# LMH.net
KiCad netlist of a schematic drawn in Altium Designer
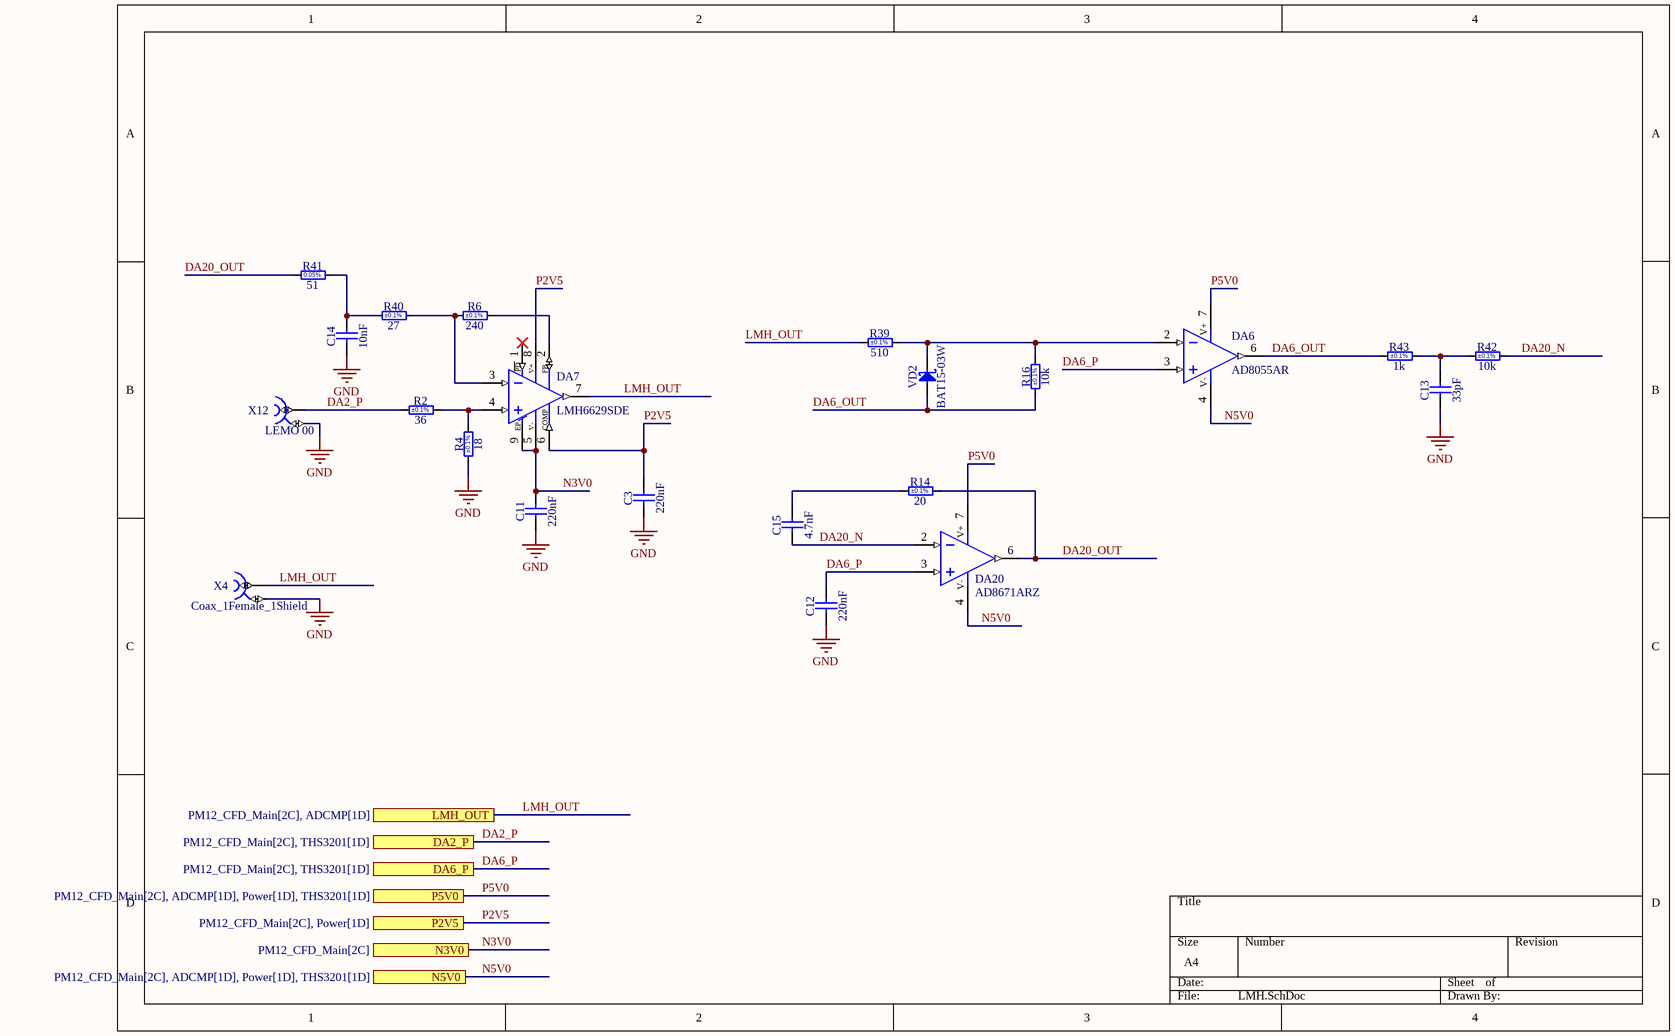
[diagram p0: LMH.SchDoc]

(export (version "E")
  (design (tool "Eeschema 10.0.6"))
  (components
    (comp (ref "C3")
      (value "220nF")
      (footprint "CAPC2012X135N")
      (description "Non-polarised capacitor")
      (fields
        (field (name "PART NUMBER") "CC0805_220NF_50V_10%_X7R")
        (field (name "VOLTAGE") "50V")
        (field (name "AUTHOR") "CERN DEM JLC")
      )
      (libsource (lib "Capacitors") (part "Capacitor - non polarized"))
    )
    (comp (ref "C11")
      (value "220nF")
      (footprint "CAPC2012X135N")
      (description "Non-polarised capacitor")
      (fields
        (field (name "PART NUMBER") "CC0805_220NF_50V_10%_X7R")
        (field (name "VOLTAGE") "50V")
        (field (name "AUTHOR") "CERN DEM JLC")
      )
      (libsource (lib "Capacitors") (part "Capacitor - non polarized"))
    )
    (comp (ref "C12")
      (value "220nF")
      (footprint "CAPC2012X135N")
      (description "Non-polarised capacitor")
      (fields
        (field (name "PART NUMBER") "CC0805_220NF_50V_10%_X7R")
        (field (name "VOLTAGE") "50V")
        (field (name "AUTHOR") "CERN DEM JLC")
      )
      (libsource (lib "Capacitors") (part "Capacitor - non polarized"))
    )
    (comp (ref "C13")
      (value "33pF")
      (footprint "CAPC2013X115N")
      (description "Non-polarised capacitor")
      (fields
        (field (name "PART NUMBER") "CC0805_33PF_200V_1%_NP0")
        (field (name "VOLTAGE") "200V")
        (field (name "AUTHOR") "CERN DEM HF")
      )
      (libsource (lib "Capacitors") (part "Capacitor - non polarized"))
    )
    (comp (ref "C14")
      (value "10nF")
      (footprint "CAPC2012X135N")
      (description "Non-polarised capacitor")
      (fields
        (field (name "PART NUMBER") "CC0805_10NF_50V_2%_C0G")
        (field (name "VOLTAGE") "50V")
        (field (name "AUTHOR") "CERN DEM HF")
      )
      (libsource (lib "Capacitors") (part "Capacitor - non polarized"))
    )
    (comp (ref "C15")
      (value "4.7nF")
      (footprint "CAPC2012X135N")
      (description "Non-polarised capacitor")
      (fields
        (field (name "PART NUMBER") "CC0805_4.7NF_250V_1%_NP0")
        (field (name "VOLTAGE") "250V")
        (field (name "AUTHOR") "CERN DEM HF")
      )
      (libsource (lib "Capacitors") (part "Capacitor - non polarized"))
    )
    (comp (ref "DA6")
      (value "AD8055AR")
      (footprint "SOIC127P600X175-8N")
      (description "Operational Amplifier")
      (fields (field (name "MANUFACTURER") "ANALOG DEVICES") (field (name "AUTHOR") "CERN DEM HF"))
      (libsource (lib "ICs And Semiconductors") (part "Operational Amplifier Type1"))
    )
    (comp (ref "DA7")
      (value "LMH6629SDE")
      (footprint "TEXAS_NGQ0008A")
      (description "Ultra-Low Noise, High-Speed Operational Amplifier with Shutdown")
      (fields (field (name "MANUFACTURER") "TEXAS INSTRUMENTS") (field (name "AUTHOR") "CERN DEM HF"))
      (libsource (lib "ICs And Semiconductors") (part "LMH6629SDE"))
    )
    (comp (ref "DA20")
      (value "AD8671ARZ")
      (footprint "SOIC127P600X175-8N")
      (description "Operational Amplifier")
      (fields
        (field (name "MANUFACTURER") "ANALOG DEVICES")
        (field (name "MANUFACTURER PART NUMBER") "AD8671AR")
        (field (name "AUTHOR") "CERN DEM JLC")
      )
      (libsource (lib "ICs And Semiconductors") (part "Operational Amplifier Type1"))
    )
    (comp (ref "R2")
      (value "36")
      (footprint "RESC1608X64N")
      (description "Resistor - 0.1%")
      (fields
        (field (name "TOLERANCE") "±0.1%")
        (field (name "PART NUMBER") "R0603_36R_0.1%_0.1W_10PPM")
        (field (name "POWER") "0.1W")
        (field (name "AUTHOR") "CERN DEM HF")
      )
      (libsource (lib "Resistors") (part "Resistor - 0.1%"))
    )
    (comp (ref "R4")
      (value "18")
      (footprint "RESC1608X64N")
      (description "Resistor - 0.1%")
      (fields
        (field (name "TOLERANCE") "±0.1%")
        (field (name "PART NUMBER") "R0603_18R_0.1%_0.1W_25PPM")
        (field (name "POWER") "0.1W")
        (field (name "AUTHOR") "CERN DEM HF")
      )
      (libsource (lib "Resistors") (part "Resistor - 0.1%"))
    )
    (comp (ref "R6")
      (value "240")
      (footprint "RESC1005X40N")
      (description "Resistor - 0.1%")
      (fields
        (field (name "TOLERANCE") "±0.1%")
        (field (name "PART NUMBER") "R0402_240R_0.1%_0.0625W_10PPM")
        (field (name "POWER") "0.063W")
        (field (name "AUTHOR") "CERN DEM HF")
      )
      (libsource (lib "Resistors") (part "Resistor - 0.1%"))
    )
    (comp (ref "R14")
      (value "20")
      (footprint "RESC2012X60N")
      (description "Resistor - 0.1%")
      (fields
        (field (name "TOLERANCE") "±0.1%")
        (field (name "PART NUMBER") "R0805_20R_0.1%_0.1W_10PPM")
        (field (name "POWER") "0.1W")
        (field (name "AUTHOR") "CERN DEM JLC")
      )
      (libsource (lib "Resistors") (part "Resistor - 0.1%"))
    )
    (comp (ref "R16")
      (value "10k")
      (footprint "RESC2012X60N")
      (description "Resistor - 0.1%")
      (fields
        (field (name "TOLERANCE") "±0.1%")
        (field (name "PART NUMBER") "R0805_10K_0.1%_0.1W_10PPM")
        (field (name "POWER") "0.1W")
        (field (name "AUTHOR") "CERN DEM JLC")
      )
      (libsource (lib "Resistors") (part "Resistor - 0.1%"))
    )
    (comp (ref "R39")
      (value "510")
      (footprint "RESC1005X40N")
      (description "Resistor - 0.1%")
      (fields
        (field (name "TOLERANCE") "±0.1%")
        (field (name "PART NUMBER") "R0402_510R_0.1%_0.0625W_10PPM")
        (field (name "POWER") "0.063W")
        (field (name "AUTHOR") "CERN DEM HF")
      )
      (libsource (lib "Resistors") (part "Resistor - 0.1%"))
    )
    (comp (ref "R40")
      (value "27")
      (footprint "RESC1608X64N")
      (description "Resistor - 0.1%")
      (fields
        (field (name "TOLERANCE") "±0.1%")
        (field (name "PART NUMBER") "R0603_27R_0.1%_0.1W_10PPM")
        (field (name "POWER") "0.1W")
        (field (name "AUTHOR") "CERN DEM HF")
      )
      (libsource (lib "Resistors") (part "Resistor - 0.1%"))
    )
    (comp (ref "R41")
      (value "51")
      (footprint "RESC2012X60N")
      (description "Resistor - 0.05%")
      (fields
        (field (name "PART NUMBER") "R0805_51R_0.05%_0.125W_10PPM")
        (field (name "POWER") "0.1W")
        (field (name "AUTHOR") "CERN DEM HF")
      )
      (libsource (lib "Resistors") (part "Resistor - 0.05%"))
    )
    (comp (ref "R42")
      (value "10k")
      (footprint "RESC2012X60N")
      (description "Resistor - 0.1%")
      (fields
        (field (name "TOLERANCE") "±0.1%")
        (field (name "PART NUMBER") "R0805_10K_0.1%_0.1W_10PPM")
        (field (name "POWER") "0.1W")
        (field (name "AUTHOR") "CERN DEM JLC")
      )
      (libsource (lib "Resistors") (part "Resistor - 0.1%"))
    )
    (comp (ref "R43")
      (value "1k")
      (footprint "RESC2012X60N")
      (description "Resistor - 0.1%")
      (fields
        (field (name "TOLERANCE") "±0.1%")
        (field (name "PART NUMBER") "R0805_1K_0.1%_0.1W_10PPM")
        (field (name "POWER") "0.1W")
        (field (name "AUTHOR") "CERN DEM JLC")
      )
      (libsource (lib "Resistors") (part "Resistor - 0.1%"))
    )
    (comp (ref "VD2")
      (value "BAT15-03W")
      (footprint "SOD2512X110N")
      (description "Schottky Diode")
      (fields
        (field (name "VOLTAGE") "4V")
        (field (name "POWER") "100mA")
        (field (name "AUTHOR") "CERN DEM HF")
      )
      (libsource (lib "ICs And Semiconductors") (part "Diode Schottky"))
    )
    (comp (ref "X4")
      (value "Coax_1Female_1Shield")
      (footprint "SAMTEC_MMCX-J-P-H-ST-TH1")
      (fields
        (field (name "PART NUMBER") "SAMTEC_MMCX-J-P-H-ST-TH1")
        (field (name "MANUFACTURER") "SAMTEC")
        (field (name "MANUFACTURER PART NUMBER") "MMCX-J-P-H-ST-TH1")
        (field (name "AUTHOR") "CERN DEM JLC")
      )
      (libsource (lib "Connectors") (part "Coax_1Female_1Shield"))
    )
    (comp (ref "X12")
      (value "LEMO 00")
      (footprint "LEMO_EPL.00.250.NTN")
      (fields
        (field (name "PART NUMBER") "LEMO_EPL.00.250.NTN")
        (field (name "MANUFACTURER") "LEMO")
        (field (name "MANUFACTURER PART NUMBER") "EPL.00.250.NTN")
        (field (name "AUTHOR") "CERN DEM JLC")
      )
      (libsource (lib "Connectors") (part "Coax_1Female_1Shield"))
    )
  )
  (nets
    (net (code "1") (name "/DA2_P") (class "Default")
      (node (ref "R2") (pin "1") (pinfunction "1_1") (pintype "passive"))
      (node (ref "X12") (pin "1") (pinfunction "1_1") (pintype "bidirectional"))
    )
    (net (code "2") (name "/DA6_OUT") (class "Default")
      (node (ref "DA6") (pin "6") (pinfunction "OUT_6") (pintype "output"))
      (node (ref "R16") (pin "1") (pinfunction "1_1") (pintype "passive"))
      (node (ref "R43") (pin "1") (pinfunction "1_1") (pintype "passive"))
      (node (ref "VD2") (pin "2") (pinfunction "A_2") (pintype "passive"))
    )
    (net (code "3") (name "/DA6_P") (class "Default")
      (node (ref "C12") (pin "2") (pinfunction "2_2") (pintype "passive"))
      (node (ref "DA20") (pin "3") (pinfunction "IN+_3") (pintype "input"))
      (node (ref "DA6") (pin "3") (pinfunction "IN+_3") (pintype "input"))
    )
    (net (code "4") (name "/DA20_N") (class "Default")
      (node (ref "C15") (pin "1") (pinfunction "1_1") (pintype "passive"))
      (node (ref "DA20") (pin "2") (pinfunction "IN-_2") (pintype "input"))
      (node (ref "R42") (pin "2") (pinfunction "2_2") (pintype "passive"))
    )
    (net (code "5") (name "/DA20_OUT") (class "Default")
      (node (ref "DA20") (pin "6") (pinfunction "OUT_6") (pintype "output"))
      (node (ref "R14") (pin "2") (pinfunction "2_2") (pintype "passive"))
      (node (ref "R41") (pin "1") (pinfunction "1_1") (pintype "passive"))
    )
    (net (code "6") (name "/LMH_OUT") (class "Default")
      (node (ref "DA7") (pin "7") (pinfunction "OUT_7") (pintype "output"))
      (node (ref "R39") (pin "1") (pinfunction "1_1") (pintype "passive"))
      (node (ref "X4") (pin "1") (pinfunction "1_1") (pintype "bidirectional"))
    )
    (net (code "7") (name "/N3V0") (class "Default")
      (node (ref "C11") (pin "2") (pinfunction "2_2") (pintype "passive"))
      (node (ref "DA7") (pin "5") (pinfunction "V-_5") (pintype "power_in"))
      (node (ref "DA7") (pin "9") (pinfunction "EP_9") (pintype "power_in"))
    )
    (net (code "8") (name "/N5V0") (class "Default")
      (node (ref "DA20") (pin "4") (pinfunction "V-_4") (pintype "power_in"))
      (node (ref "DA6") (pin "4") (pinfunction "V-_4") (pintype "power_in"))
    )
    (net (code "9") (name "/P2V5") (class "Default")
      (node (ref "C3") (pin "2") (pinfunction "2_2") (pintype "passive"))
      (node (ref "DA7") (pin "6") (pinfunction "COMP_6") (pintype "input"))
      (node (ref "DA7") (pin "8") (pinfunction "V+_8") (pintype "power_in"))
    )
    (net (code "10") (name "/P5V0") (class "Default")
      (node (ref "DA20") (pin "7") (pinfunction "V+_7") (pintype "power_in"))
      (node (ref "DA6") (pin "7") (pinfunction "V+_7") (pintype "power_in"))
    )
    (net (code "11") (name "GND") (class "Default")
      (node (ref "C11") (pin "1") (pinfunction "1_1") (pintype "passive"))
      (node (ref "C12") (pin "1") (pinfunction "1_1") (pintype "passive"))
      (node (ref "C13") (pin "1") (pinfunction "1_1") (pintype "passive"))
      (node (ref "C14") (pin "1") (pinfunction "1_1") (pintype "passive"))
      (node (ref "C3") (pin "1") (pinfunction "1_1") (pintype "passive"))
      (node (ref "R4") (pin "1") (pinfunction "1_1") (pintype "passive"))
      (node (ref "X12") (pin "2") (pinfunction "2_2") (pintype "bidirectional"))
      (node (ref "X4") (pin "2") (pinfunction "2_2") (pintype "bidirectional"))
    )
    (net (code "12") (name "Net-(C13-Pad2)") (class "Default")
      (node (ref "C13") (pin "2") (pinfunction "2_2") (pintype "passive"))
      (node (ref "R42") (pin "1") (pinfunction "1_1") (pintype "passive"))
      (node (ref "R43") (pin "2") (pinfunction "2_2") (pintype "passive"))
    )
    (net (code "13") (name "Net-(C14-Pad2)") (class "Default")
      (node (ref "C14") (pin "2") (pinfunction "2_2") (pintype "passive"))
      (node (ref "R40") (pin "1") (pinfunction "1_1") (pintype "passive"))
      (node (ref "R41") (pin "2") (pinfunction "2_2") (pintype "passive"))
    )
    (net (code "14") (name "Net-(C15-Pad2)") (class "Default")
      (node (ref "C15") (pin "2") (pinfunction "2_2") (pintype "passive"))
      (node (ref "R14") (pin "1") (pinfunction "1_1") (pintype "passive"))
    )
    (net (code "15") (name "Net-(DA6-IN-)") (class "Default")
      (node (ref "DA6") (pin "2") (pinfunction "IN-_2") (pintype "input"))
      (node (ref "R16") (pin "2") (pinfunction "2_2") (pintype "passive"))
      (node (ref "R39") (pin "2") (pinfunction "2_2") (pintype "passive"))
      (node (ref "VD2") (pin "1") (pinfunction "C_1") (pintype "passive"))
    )
    (net (code "16") (name "Net-(DA7-FB)") (class "Default")
      (node (ref "DA7") (pin "2") (pinfunction "FB_2") (pintype "bidirectional"))
      (node (ref "R6") (pin "2") (pinfunction "2_2") (pintype "passive"))
    )
    (net (code "17") (name "Net-(DA7-IN+)") (class "Default")
      (node (ref "DA7") (pin "4") (pinfunction "IN+_4") (pintype "input"))
      (node (ref "R2") (pin "2") (pinfunction "2_2") (pintype "passive"))
      (node (ref "R4") (pin "2") (pinfunction "2_2") (pintype "passive"))
    )
    (net (code "18") (name "Net-(DA7-IN-)") (class "Default")
      (node (ref "DA7") (pin "3") (pinfunction "IN-_3") (pintype "input"))
      (node (ref "R40") (pin "2") (pinfunction "2_2") (pintype "passive"))
      (node (ref "R6") (pin "1") (pinfunction "1_1") (pintype "passive"))
    )
    (net (code "19") (name "unconnected-(DA7-~{PD}-Pad1)") (class "Default")
      (node (ref "DA7") (pin "1") (pinfunction "~{PD}_1") (pintype "input+no_connect"))
    )
  )
)
